# ESP01_Relay.net
KiCad netlist of a schematic drawn in Altium Designer
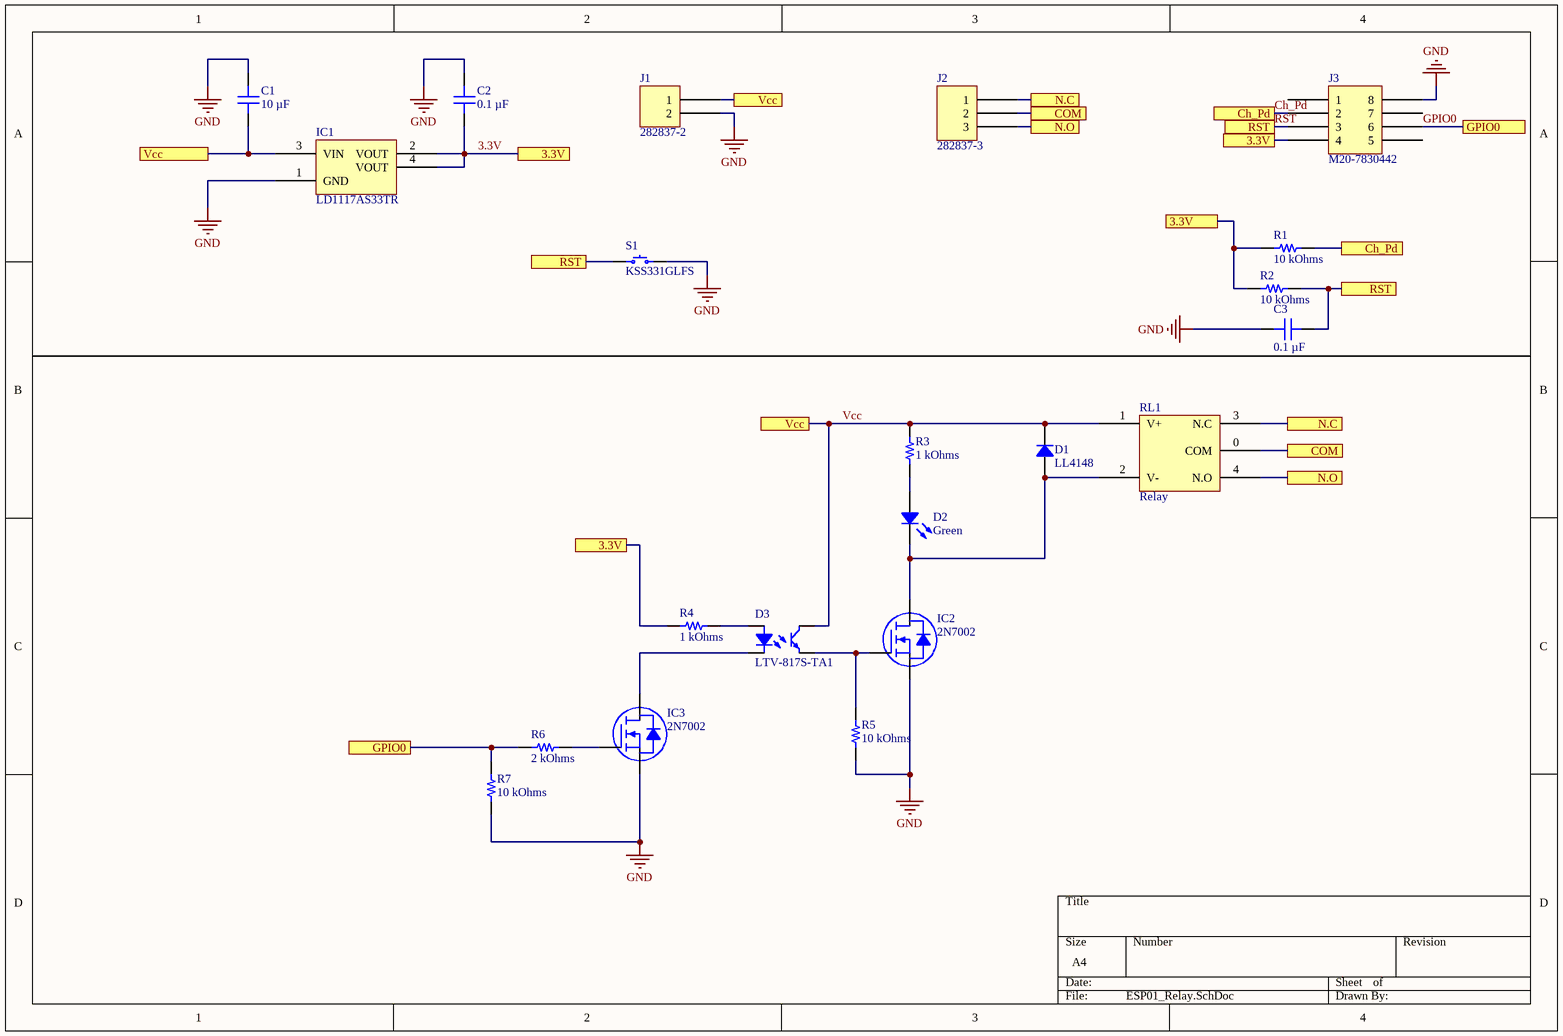
[diagram p0: ESP01_Relay.SchDoc]

(export (version "E")
  (design (tool "Eeschema 10.0.6"))
  (components
    (comp (ref "C1")
      (value "10 µF")
      (footprint "CAP 1206_3216 - 0.8MM")
      (description "CAP CER 10UF 16V X7R 1206")
      (fields
        (field (name "PART NUMBER") "1206B106K160CT")
        (field (name "MANUFACTURER") "Walsin Technology Corporation")
      )
      (libsource (lib "Celestial Altium Library - altium_library") (part "Capacitor"))
    )
    (comp (ref "C2")
      (value "0.1 µF")
      (footprint "CAP 1206_3216 - 0.8MM")
      (description "CAP CER 0.1UF 50V X7R 1206")
      (fields
        (field (name "PART NUMBER") "1206B104J500CT")
        (field (name "MANUFACTURER") "Walsin Technology Corporation")
      )
      (libsource (lib "Celestial Altium Library - altium_library") (part "Capacitor"))
    )
    (comp (ref "C3")
      (value "0.1 µF")
      (footprint "CAP 0805_2012")
      (description "CAP CER 0.1UF 50V X7R 0805")
      (fields (field (name "PART NUMBER") "CC0805MRX7R9BB104") (field (name "MANUFACTURER") "Yageo"))
      (libsource (lib "Celestial Altium Library - altium_library") (part "Capacitor"))
    )
    (comp (ref "D1")
      (value "LL4148")
      (footprint "SOD-80 MiniMELF")
      (description "DIODE GEN PURP 100V 200MA SOD80")
      (fields (field (name "MANUFACTURER") "ON Semiconductor"))
      (libsource (lib "Celestial Altium Library - altium_library") (part "Diode"))
    )
    (comp (ref "D2")
      (value "Green")
      (footprint "LED 1206_3216 GREEN")
      (description "LED GREEN CLEAR 2SMD")
      (fields (field (name "PART NUMBER") "XZVG55W-A2") (field (name "MANUFACTURER") "SunLED"))
      (libsource (lib "Celestial Altium Library - altium_library") (part "LED"))
    )
    (comp (ref "D3")
      (value "LTV-817S-TA1")
      (footprint "LITEON LTV-817")
      (description "OPTOISOLATR 5KV TRANSISTOR 4-SMD")
      (fields (field (name "MANUFACTURER") "Lite-On Inc."))
      (libsource (lib "Celestial Altium Library - altium_library") (part "Optoisolator"))
    )
    (comp (ref "IC1")
      (value "LD1117AS33TR")
      (footprint "ST SOT-223")
      (description "IC REG LINEAR 3.3V 1A SOT223")
      (fields (field (name "MANUFACTURER") "STMicroelectronics"))
      (libsource (lib "Celestial Altium Library - altium_library") (part "ST LD1117"))
    )
    (comp (ref "IC2")
      (value "2N7002")
      (footprint "ON SEMI SOT-23-3")
      (description "MOSFET N-CH 60V 115MA SOT-23")
      (fields (field (name "MANUFACTURER") "ON Semiconductor"))
      (libsource (lib "Celestial Altium Library - altium_library") (part "ON SEMI MOSFET N-CH SOT-23-3"))
    )
    (comp (ref "IC3")
      (value "2N7002")
      (footprint "ON SEMI SOT-23-3")
      (description "MOSFET N-CH 60V 115MA SOT-23")
      (fields (field (name "MANUFACTURER") "ON Semiconductor"))
      (libsource (lib "Celestial Altium Library - altium_library") (part "ON SEMI MOSFET N-CH SOT-23-3"))
    )
    (comp (ref "J1")
      (value "282837-2")
      (footprint "TE 282837-2")
      (description "TERM BLK 2P SIDE ENT 5.08MM PCB")
      (fields (field (name "MANUFACTURER") "TE Connectivity AMP Connectors") (field (name "VOLTAGE") "300 V"))
      (libsource (lib "Celestial Altium Library - altium_library") (part "2 Pin"))
    )
    (comp (ref "J2")
      (value "282837-3")
      (footprint "TE 282837-3")
      (description "TERM BLK 3P SIDE ENT 5.08MM PCB")
      (fields (field (name "MANUFACTURER") "TE Connectivity AMP Connectors") (field (name "VOLTAGE") "300 V"))
      (libsource (lib "Celestial Altium Library - altium_library") (part "3 Pin"))
    )
    (comp (ref "J3")
      (value "M20-7830442")
      (footprint "HARWIN M20-7830445")
      (description "CONN RCPT 8POS 0.1 GOLD PCB")
      (fields (field (name "MANUFACTURER") "Harwin Inc."))
      (libsource (lib "Celestial Altium Library - altium_library") (part "2X4 PIN DU"))
    )
    (comp (ref "R1")
      (value "10 kOhms")
      (footprint "RES 1206_3216")
      (description "RES 10K OHM 1% 1/4W 1206")
      (fields
        (field (name "PART NUMBER") "CRGCQ1206F10K")
        (field (name "MANUFACTURER") "TE Connectivity Passive Product")
      )
      (libsource (lib "Celestial Altium Library - altium_library") (part "Resistor"))
    )
    (comp (ref "R2")
      (value "10 kOhms")
      (footprint "RES 1206_3216")
      (description "RES 10K OHM 1% 1/4W 1206")
      (fields
        (field (name "PART NUMBER") "CRGCQ1206F10K")
        (field (name "MANUFACTURER") "TE Connectivity Passive Product")
      )
      (libsource (lib "Celestial Altium Library - altium_library") (part "Resistor"))
    )
    (comp (ref "R3")
      (value "1 kOhms")
      (footprint "RES 1206_3216")
      (description "RES SMD 1K OHM 5% 1/4W 1206")
      (fields (field (name "PART NUMBER") "KTR18EZPJ102") (field (name "MANUFACTURER") "Rohm Semiconductor"))
      (libsource (lib "Celestial Altium Library - altium_library") (part "Resistor"))
    )
    (comp (ref "R4")
      (value "1 kOhms")
      (footprint "RES 1206_3216")
      (description "RES SMD 1K OHM 5% 1/4W 1206")
      (fields (field (name "PART NUMBER") "KTR18EZPJ102") (field (name "MANUFACTURER") "Rohm Semiconductor"))
      (libsource (lib "Celestial Altium Library - altium_library") (part "Resistor"))
    )
    (comp (ref "R5")
      (value "10 kOhms")
      (footprint "RES 1206_3216")
      (description "RES 10K OHM 1% 1/4W 1206")
      (fields
        (field (name "PART NUMBER") "CRGCQ1206F10K")
        (field (name "MANUFACTURER") "TE Connectivity Passive Product")
      )
      (libsource (lib "Celestial Altium Library - altium_library") (part "Resistor"))
    )
    (comp (ref "R6")
      (value "2 kOhms")
      (footprint "RES 1206_3216")
      (description "RES SMD 2K OHM 5% 1/4W 1206")
      (fields (field (name "PART NUMBER") "AC1206JR-072KL") (field (name "MANUFACTURER") "Yageo"))
      (libsource (lib "Celestial Altium Library - altium_library") (part "Resistor"))
    )
    (comp (ref "R7")
      (value "10 kOhms")
      (footprint "RES 1206_3216")
      (description "RES 10K OHM 1% 1/4W 1206")
      (fields
        (field (name "PART NUMBER") "CRGCQ1206F10K")
        (field (name "MANUFACTURER") "TE Connectivity Passive Product")
      )
      (libsource (lib "Celestial Altium Library - altium_library") (part "Resistor"))
    )
    (comp (ref "RL1")
      (value "Relay")
      (footprint "Relay")
      (description "Relay 5v 5 pin")
      (libsource (lib "Schlib1") (part "Relay"))
    )
    (comp (ref "S1")
      (value "KSS331GLFS")
      (footprint "C&K KSS")
      (description "SWITCH TACTILE SPST-NO 0.05A 50V")
      (fields (field (name "MANUFACTURER") "C&K"))
      (libsource (lib "Celestial Altium Library - altium_library") (part "SPST-NO 2 PIN"))
    )
  )
  (nets
    (net (code "1") (name "/3.3V") (class "Default")
      (node (ref "C2") (pin "2") (pinfunction "2_2") (pintype "passive"))
      (node (ref "IC1") (pin "2") (pinfunction "VOUT_2") (pintype "passive"))
      (node (ref "IC1") (pin "4") (pinfunction "VOUT_4") (pintype "passive"))
      (node (ref "J3") (pin "4") (pinfunction "4_4") (pintype "passive"))
      (node (ref "R1") (pin "1") (pinfunction "1_1") (pintype "passive"))
      (node (ref "R2") (pin "1") (pinfunction "1_1") (pintype "passive"))
      (node (ref "R4") (pin "2") (pinfunction "2_2") (pintype "passive"))
    )
    (net (code "2") (name "/COM") (class "Default")
      (node (ref "J2") (pin "2") (pinfunction "2_2") (pintype "passive"))
      (node (ref "RL1") (pin "0") (pinfunction "COM_0") (pintype "passive"))
    )
    (net (code "3") (name "/Ch_Pd") (class "Default")
      (node (ref "J3") (pin "2") (pinfunction "2_2") (pintype "passive"))
      (node (ref "R1") (pin "2") (pinfunction "2_2") (pintype "passive"))
    )
    (net (code "4") (name "/GPIO0") (class "Default")
      (node (ref "J3") (pin "6") (pinfunction "6_6") (pintype "passive"))
      (node (ref "R6") (pin "1") (pinfunction "1_1") (pintype "passive"))
      (node (ref "R7") (pin "2") (pinfunction "2_2") (pintype "passive"))
    )
    (net (code "5") (name "/N.C") (class "Default")
      (node (ref "J2") (pin "1") (pinfunction "1_1") (pintype "passive"))
      (node (ref "RL1") (pin "3") (pinfunction "N.C_3") (pintype "passive"))
    )
    (net (code "6") (name "/N.O") (class "Default")
      (node (ref "J2") (pin "3") (pinfunction "3_3") (pintype "passive"))
      (node (ref "RL1") (pin "4") (pinfunction "N.O_4") (pintype "passive"))
    )
    (net (code "7") (name "/RST") (class "Default")
      (node (ref "C3") (pin "2") (pinfunction "2_2") (pintype "passive"))
      (node (ref "J3") (pin "3") (pinfunction "3_3") (pintype "passive"))
      (node (ref "R2") (pin "2") (pinfunction "2_2") (pintype "passive"))
      (node (ref "S1") (pin "1") (pinfunction "1_1") (pintype "passive"))
    )
    (net (code "8") (name "/Vcc") (class "Default")
      (node (ref "C1") (pin "2") (pinfunction "2_2") (pintype "passive"))
      (node (ref "D1") (pin "2") (pinfunction "2_2") (pintype "passive"))
      (node (ref "D3") (pin "4") (pinfunction "4_4") (pintype "passive"))
      (node (ref "IC1") (pin "3") (pinfunction "VIN_3") (pintype "passive"))
      (node (ref "J1") (pin "1") (pinfunction "1_1") (pintype "passive"))
      (node (ref "R3") (pin "2") (pinfunction "2_2") (pintype "passive"))
      (node (ref "RL1") (pin "1") (pinfunction "V+_1") (pintype "passive"))
    )
    (net (code "9") (name "GND") (class "Default")
      (node (ref "C1") (pin "1") (pinfunction "1_1") (pintype "passive"))
      (node (ref "C2") (pin "1") (pinfunction "1_1") (pintype "passive"))
      (node (ref "C3") (pin "1") (pinfunction "1_1") (pintype "passive"))
      (node (ref "IC1") (pin "1") (pinfunction "GND_1") (pintype "passive"))
      (node (ref "IC2") (pin "2") (pinfunction "S_2") (pintype "passive"))
      (node (ref "IC3") (pin "2") (pinfunction "S_2") (pintype "passive"))
      (node (ref "J1") (pin "2") (pinfunction "2_2") (pintype "passive"))
      (node (ref "J3") (pin "8") (pinfunction "8_8") (pintype "passive"))
      (node (ref "R5") (pin "1") (pinfunction "1_1") (pintype "passive"))
      (node (ref "R7") (pin "1") (pinfunction "1_1") (pintype "passive"))
      (node (ref "S1") (pin "2") (pinfunction "2_2") (pintype "passive"))
    )
    (net (code "10") (name "Net-(D2-Pad1)") (class "Default")
      (node (ref "D2") (pin "1") (pinfunction "1_1") (pintype "passive"))
      (node (ref "R3") (pin "1") (pinfunction "1_1") (pintype "passive"))
    )
    (net (code "11") (name "Net-(D3-Pad1)") (class "Default")
      (node (ref "D3") (pin "1") (pinfunction "1_1") (pintype "passive"))
      (node (ref "R4") (pin "1") (pinfunction "1_1") (pintype "passive"))
    )
    (net (code "12") (name "Net-(IC2-D)") (class "Default")
      (node (ref "D1") (pin "1") (pinfunction "1_1") (pintype "passive"))
      (node (ref "D2") (pin "2") (pinfunction "2_2") (pintype "passive"))
      (node (ref "IC2") (pin "3") (pinfunction "D_3") (pintype "passive"))
      (node (ref "RL1") (pin "2") (pinfunction "V-_2") (pintype "passive"))
    )
    (net (code "13") (name "Net-(IC2-G)") (class "Default")
      (node (ref "D3") (pin "3") (pinfunction "3_3") (pintype "passive"))
      (node (ref "IC2") (pin "1") (pinfunction "G_1") (pintype "passive"))
      (node (ref "R5") (pin "2") (pinfunction "2_2") (pintype "passive"))
    )
    (net (code "14") (name "Net-(IC3-D)") (class "Default")
      (node (ref "D3") (pin "2") (pinfunction "2_2") (pintype "passive"))
      (node (ref "IC3") (pin "3") (pinfunction "D_3") (pintype "passive"))
    )
    (net (code "15") (name "Net-(IC3-G)") (class "Default")
      (node (ref "IC3") (pin "1") (pinfunction "G_1") (pintype "passive"))
      (node (ref "R6") (pin "2") (pinfunction "2_2") (pintype "passive"))
    )
    (net (code "16") (name "unconnected-(J3-Pad1)") (class "Default")
      (node (ref "J3") (pin "1") (pinfunction "1_1") (pintype "passive"))
    )
    (net (code "17") (name "unconnected-(J3-Pad5)") (class "Default")
      (node (ref "J3") (pin "5") (pinfunction "5_5") (pintype "passive"))
    )
    (net (code "18") (name "unconnected-(J3-Pad7)") (class "Default")
      (node (ref "J3") (pin "7") (pinfunction "7_7") (pintype "passive"))
    )
  )
)
